# flea.net
KiCad netlist of a schematic drawn in EAGLE
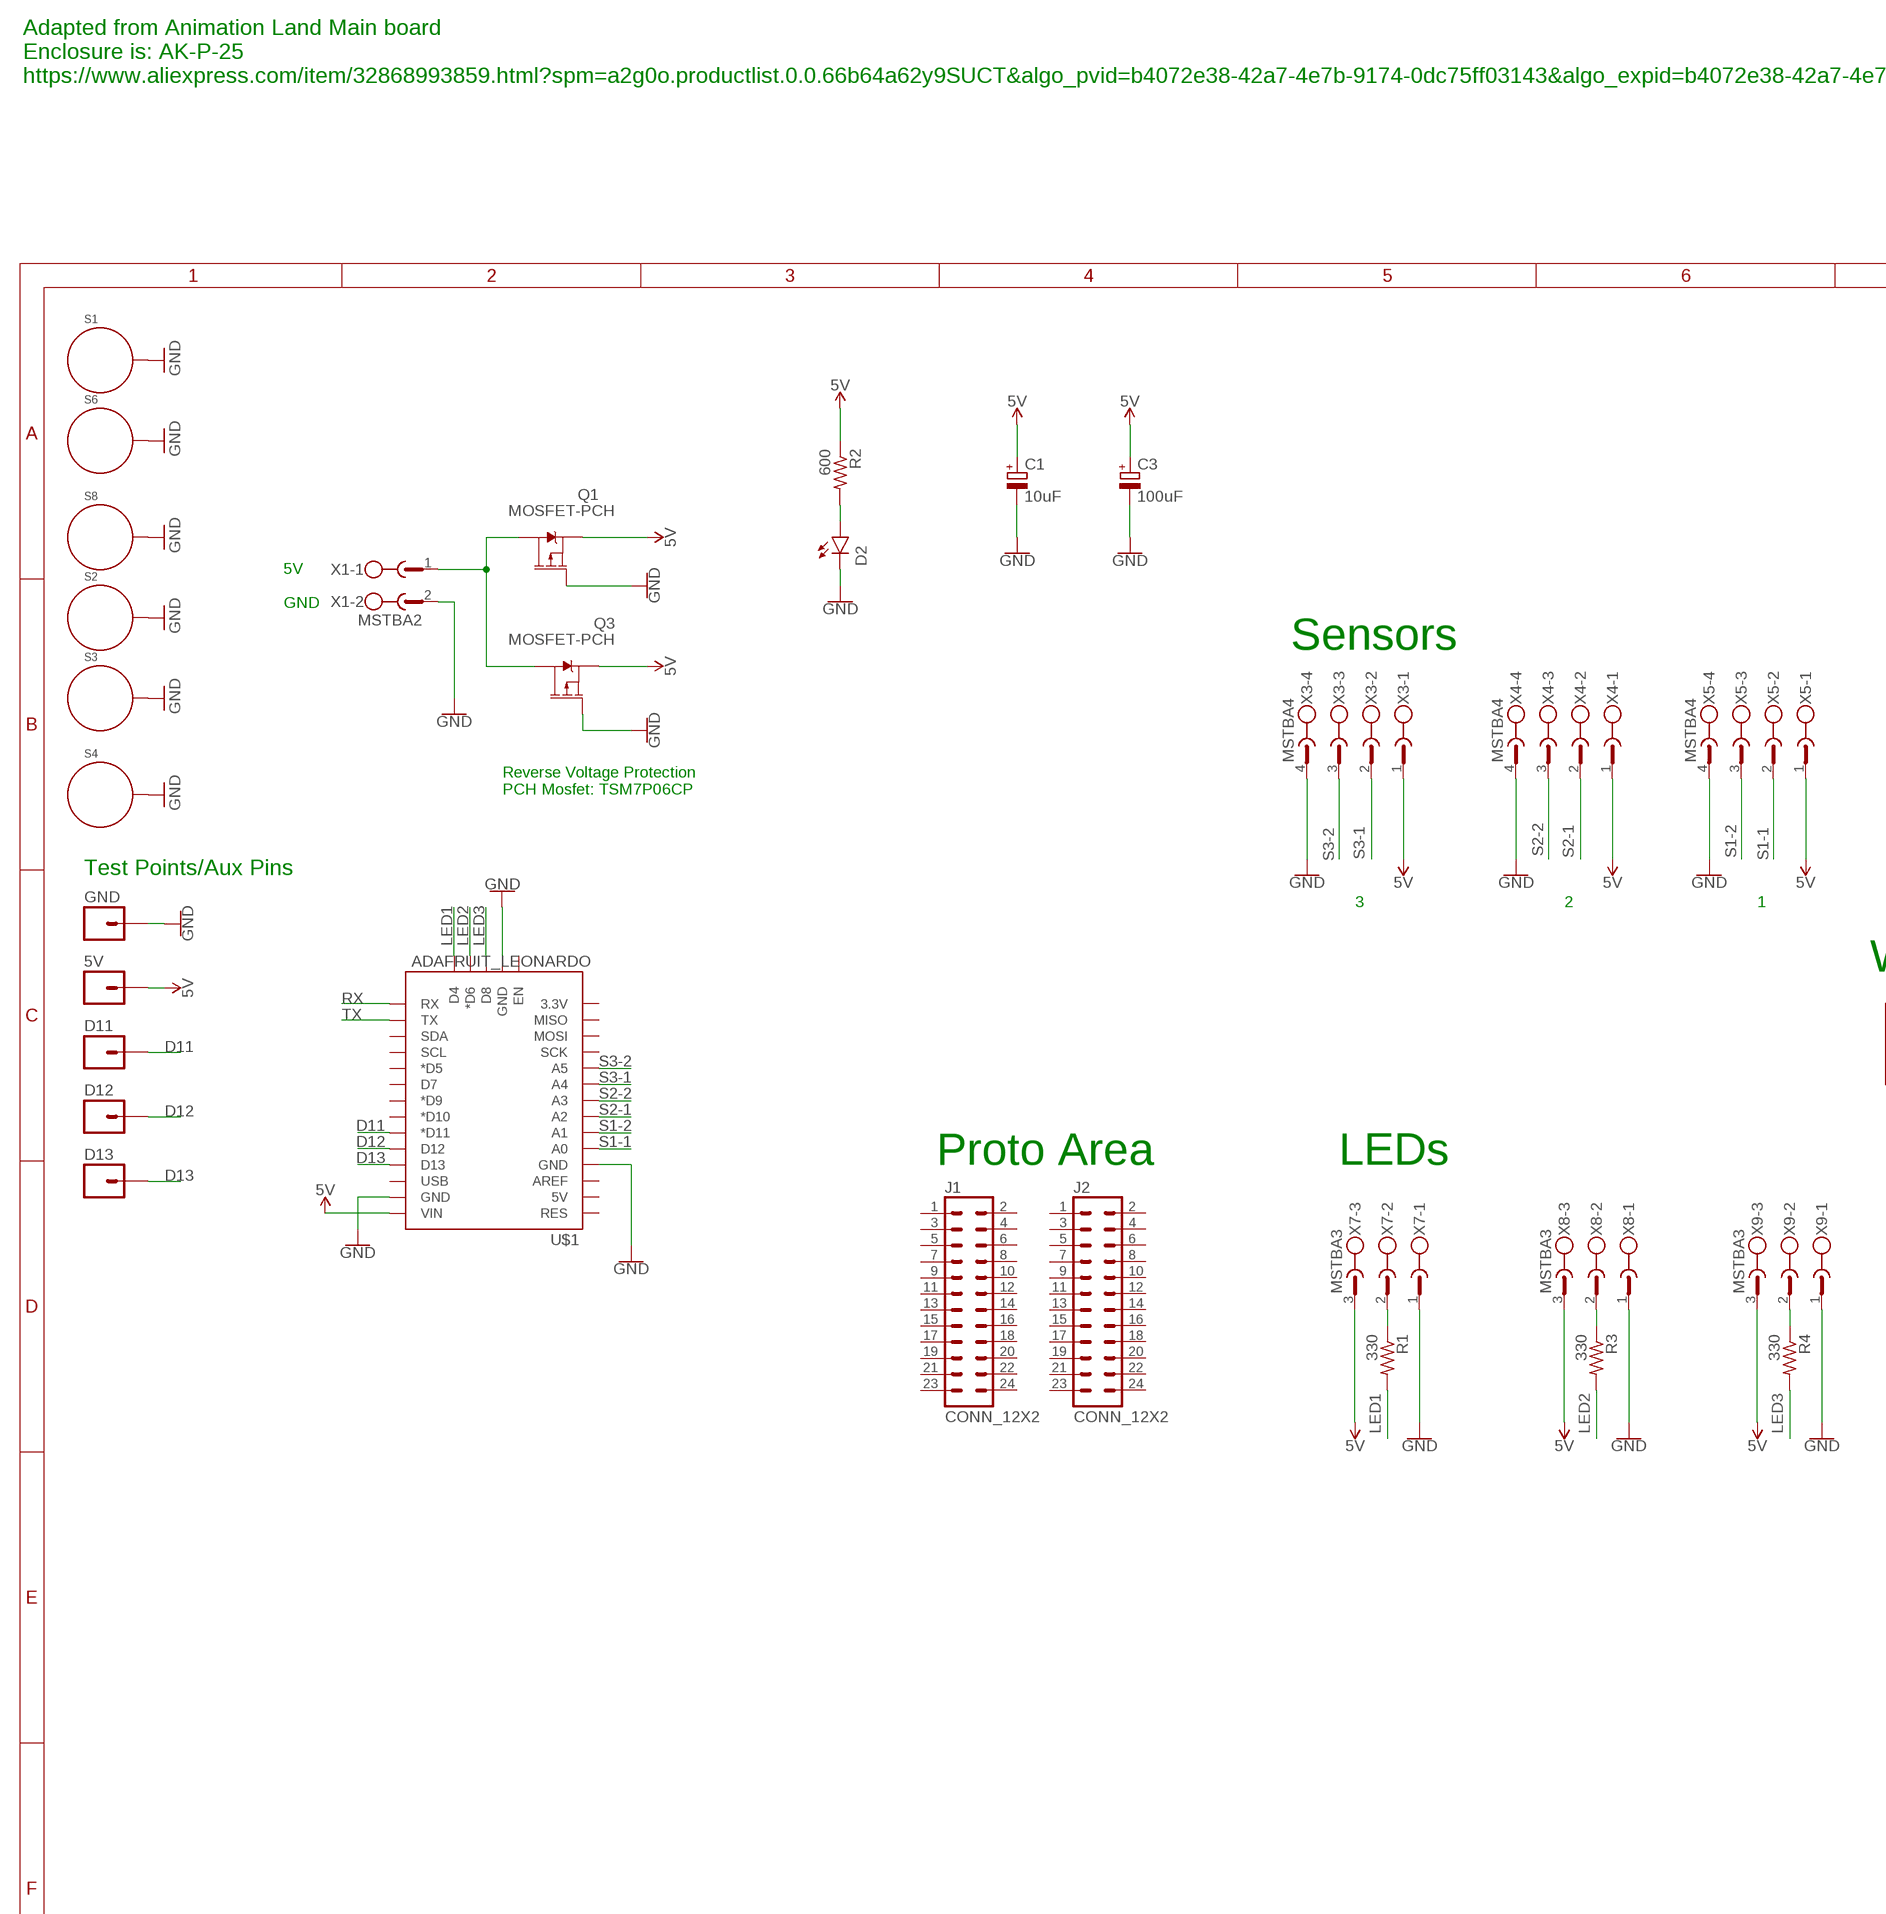
[diagram p0: schematic, sheet 1, part 1 of 2]
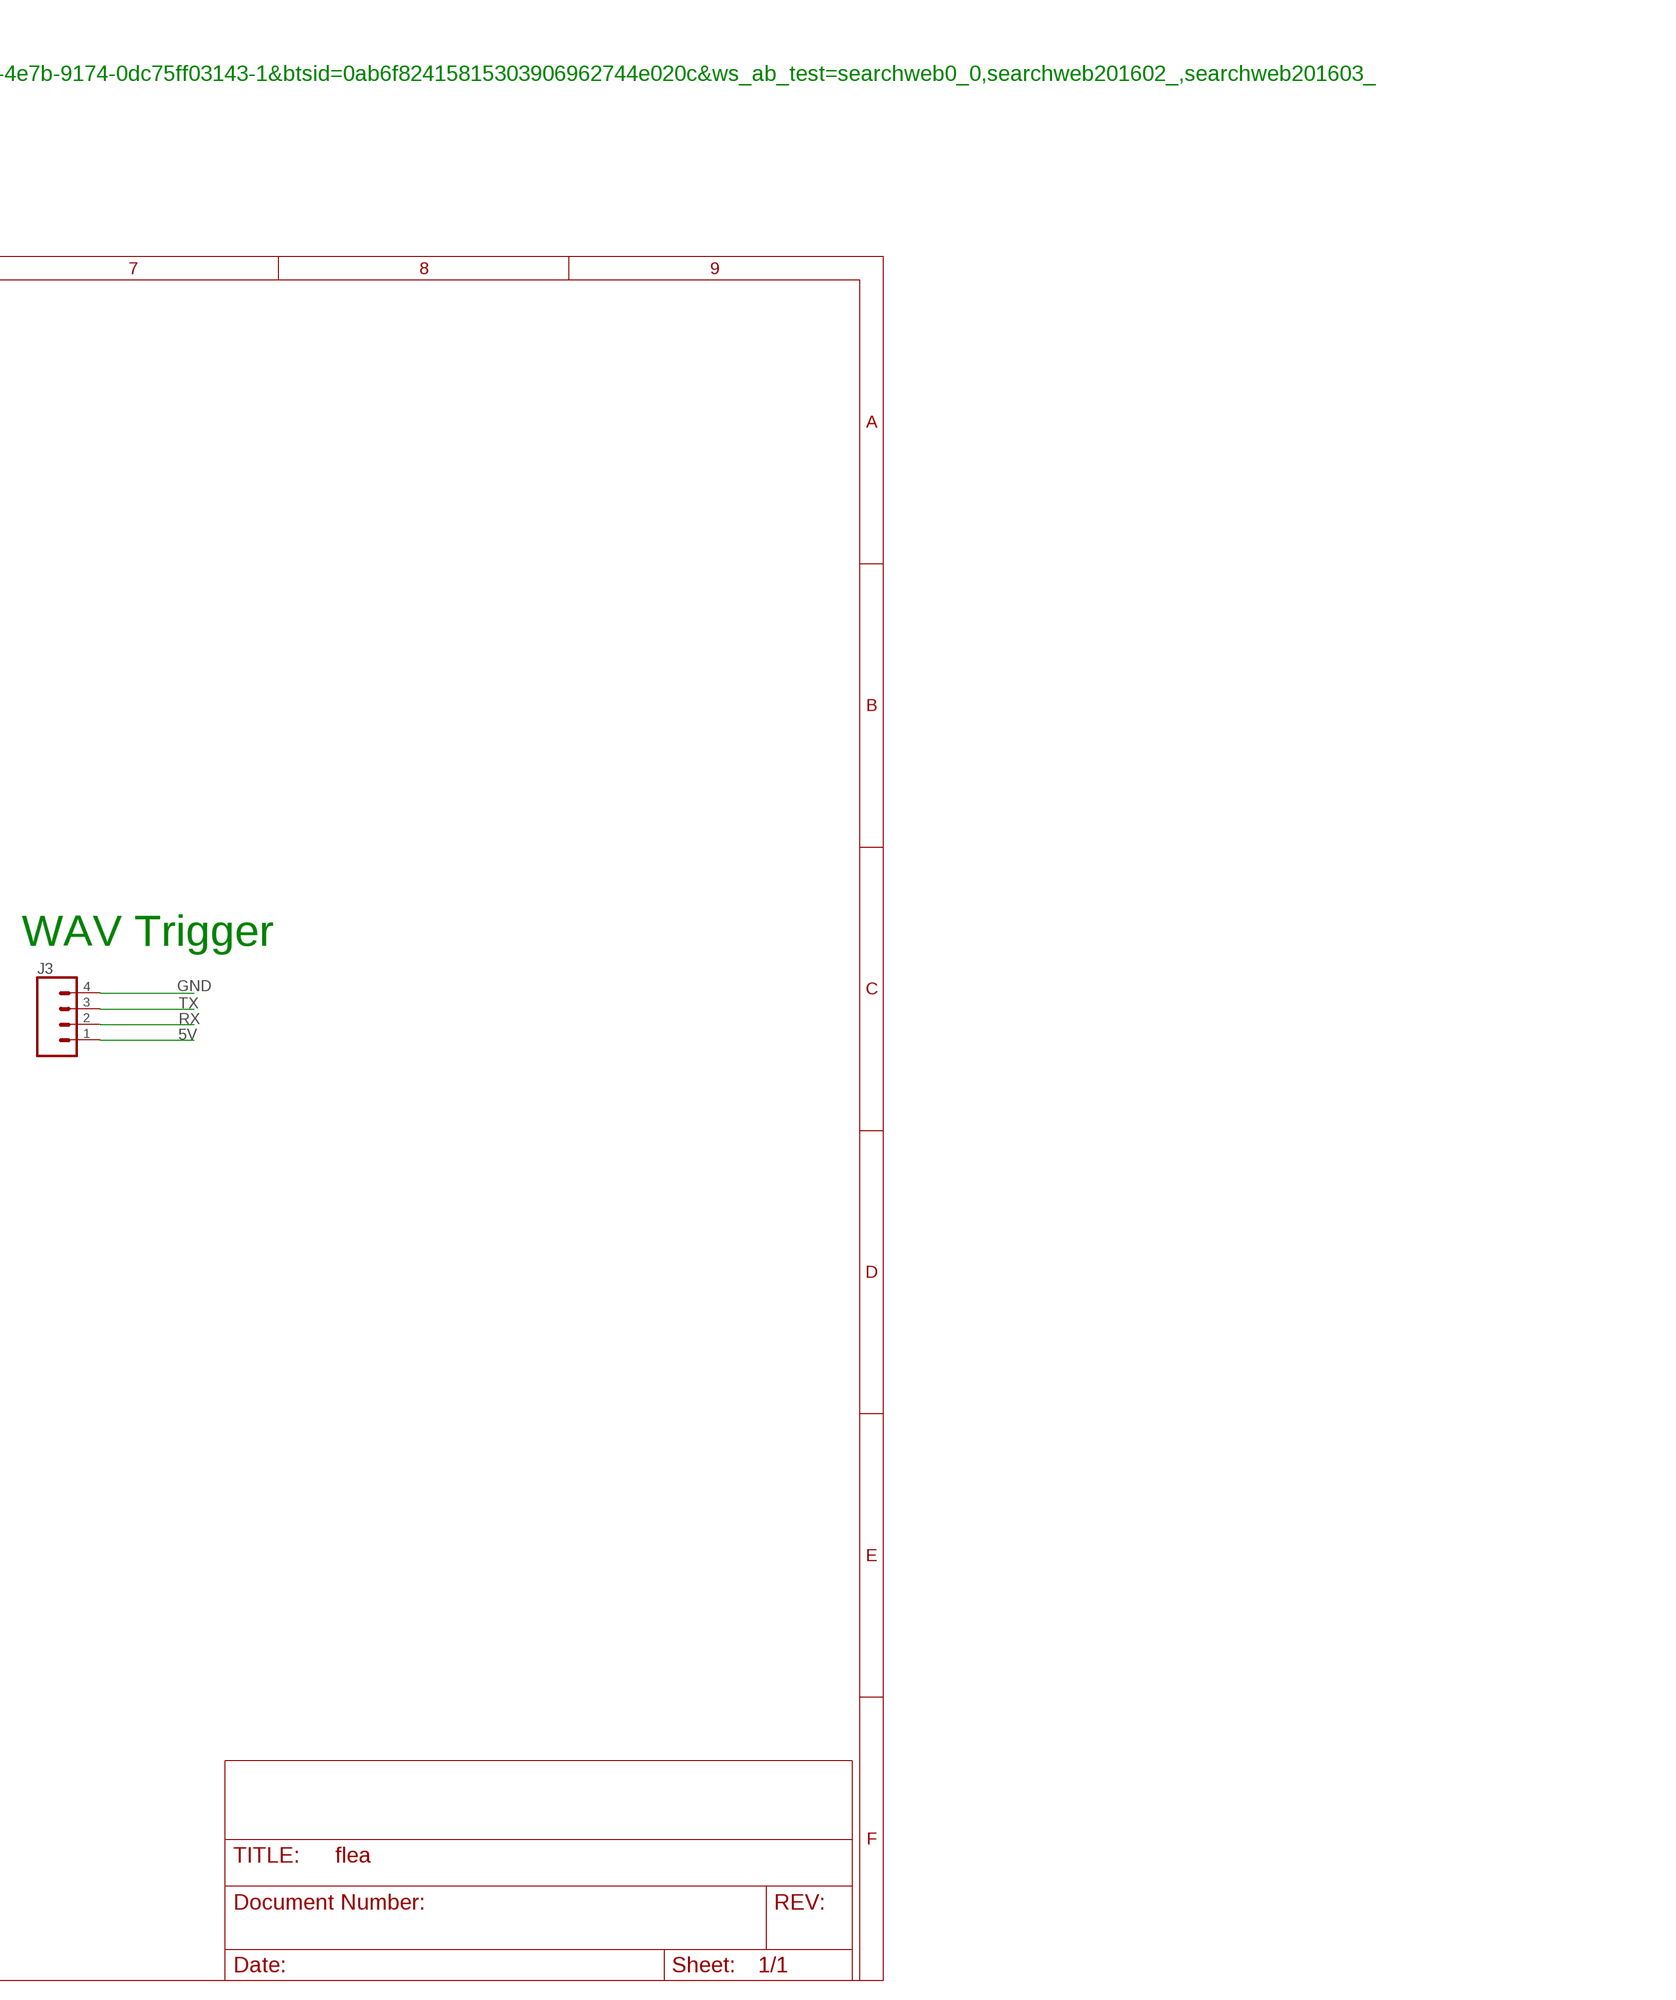
[diagram p1: schematic, sheet 1, part 2 of 2]

(export (version "E")
  (design (tool "Eeschema 10.0.6"))
  (components
    (comp (ref "5V")
      (value "M01PTH")
      (footprint "eagle-import:1X01")
      (libsource (lib "eagle-import") (part "M01PTH"))
    )
    (comp (ref "C1")
      (value "10uF")
      (footprint "eagle-import:E2-5")
      (libsource (lib "eagle-import") (part "CPOL-EUE2-5"))
    )
    (comp (ref "C3")
      (value "100uF")
      (footprint "eagle-import:E3,5-10")
      (libsource (lib "eagle-import") (part "CPOL-EUE3.5-10"))
    )
    (comp (ref "D2")
      (value "RED")
      (footprint "eagle-import:SPARKFUN-LED_LED-1206")
      (libsource (lib "eagle-import") (part "SPARKFUN-LED_LED1206"))
    )
    (comp (ref "D11")
      (value "M01PTH")
      (footprint "eagle-import:1X01")
      (libsource (lib "eagle-import") (part "M01PTH"))
    )
    (comp (ref "D12")
      (value "M01PTH")
      (footprint "eagle-import:1X01")
      (libsource (lib "eagle-import") (part "M01PTH"))
    )
    (comp (ref "D13")
      (value "M01PTH")
      (footprint "eagle-import:1X01")
      (libsource (lib "eagle-import") (part "M01PTH"))
    )
    (comp (ref "GND")
      (value "M01PTH")
      (footprint "eagle-import:1X01")
      (libsource (lib "eagle-import") (part "M01PTH"))
    )
    (comp (ref "J1")
      (value "CONN_12X2")
      (footprint "eagle-import:2X12")
      (libsource (lib "eagle-import") (part "CONN_12X2"))
    )
    (comp (ref "J2")
      (value "CONN_12X2")
      (footprint "eagle-import:2X12")
      (libsource (lib "eagle-import") (part "CONN_12X2"))
    )
    (comp (ref "J3")
      (value "CONN_043.5MM_RA")
      (footprint "eagle-import:1X04_3.5MM_RA")
      (libsource (lib "eagle-import") (part "CONN_043.5MM_RA"))
    )
    (comp (ref "Q1")
      (value "MOSFET-PCH")
      (footprint "eagle-import:DPAK")
      (libsource (lib "eagle-import") (part "MOSFET-PCH"))
    )
    (comp (ref "Q3")
      (value "MOSFET-PCH")
      (footprint "eagle-import:DPAK")
      (libsource (lib "eagle-import") (part "MOSFET-PCH"))
    )
    (comp (ref "R1")
      (value "330")
      (footprint "eagle-import:R0805")
      (libsource (lib "eagle-import") (part "R-US_R0805"))
    )
    (comp (ref "R2")
      (value "600")
      (footprint "eagle-import:R0805")
      (libsource (lib "eagle-import") (part "R-US_R0805"))
    )
    (comp (ref "R3")
      (value "330")
      (footprint "eagle-import:R0805")
      (libsource (lib "eagle-import") (part "R-US_R0805"))
    )
    (comp (ref "R4")
      (value "330")
      (footprint "eagle-import:R0805")
      (libsource (lib "eagle-import") (part "R-US_R0805"))
    )
    (comp (ref "S1")
      (value "STANDOFF_ELECTRICAL5-32")
      (footprint "eagle-import:STANDOFF_ELECTRICAL_5_32")
      (libsource (lib "eagle-import") (part "STANDOFF_ELECTRICAL5-32"))
    )
    (comp (ref "S2")
      (value "STANDOFF_ELECTRICAL5-32")
      (footprint "eagle-import:STANDOFF_ELECTRICAL_5_32")
      (libsource (lib "eagle-import") (part "STANDOFF_ELECTRICAL5-32"))
    )
    (comp (ref "S3")
      (value "STANDOFF_ELECTRICAL5-32")
      (footprint "eagle-import:STANDOFF_ELECTRICAL_5_32")
      (libsource (lib "eagle-import") (part "STANDOFF_ELECTRICAL5-32"))
    )
    (comp (ref "S4")
      (value "STANDOFF_ELECTRICAL5-32")
      (footprint "eagle-import:STANDOFF_ELECTRICAL_5_32")
      (libsource (lib "eagle-import") (part "STANDOFF_ELECTRICAL5-32"))
    )
    (comp (ref "S6")
      (value "STANDOFF_ELECTRICAL5-32")
      (footprint "eagle-import:STANDOFF_ELECTRICAL_5_32")
      (libsource (lib "eagle-import") (part "STANDOFF_ELECTRICAL5-32"))
    )
    (comp (ref "S8")
      (value "STANDOFF_ELECTRICAL5-32")
      (footprint "eagle-import:STANDOFF_ELECTRICAL_5_32")
      (libsource (lib "eagle-import") (part "STANDOFF_ELECTRICAL5-32"))
    )
    (comp (ref "U$1")
      (value "ADAFRUIT_LEONARDO")
      (footprint "eagle-import:ADAFRUIT_LENOARDO")
      (libsource (lib "eagle-import") (part "ADAFRUIT_LEONARDO"))
    )
    (comp (ref "X1")
      (value "MSTBA2")
      (footprint "eagle-import:MSTBA2")
      (fields (field (name "MF") "FARNELL") (field (name "MPN") "1757242"))
      (libsource (lib "eagle-import") (part "MSTBA2"))
    )
    (comp (ref "X3")
      (value "MSTBA4")
      (footprint "eagle-import:MSTBA4")
      (fields (field (name "MF") "FARNELL") (field (name "MPN") "1757268"))
      (libsource (lib "eagle-import") (part "MSTBA4"))
    )
    (comp (ref "X4")
      (value "MSTBA4")
      (footprint "eagle-import:MSTBA4")
      (fields (field (name "MF") "FARNELL") (field (name "MPN") "1757268"))
      (libsource (lib "eagle-import") (part "MSTBA4"))
    )
    (comp (ref "X5")
      (value "MSTBA4")
      (footprint "eagle-import:MSTBA4")
      (fields (field (name "MF") "FARNELL") (field (name "MPN") "1757268"))
      (libsource (lib "eagle-import") (part "MSTBA4"))
    )
    (comp (ref "X7")
      (value "MSTBA3")
      (footprint "eagle-import:MSTBA3")
      (fields (field (name "MF") "FARNELL") (field (name "MPN") "1757255"))
      (libsource (lib "eagle-import") (part "MSTBA3"))
    )
    (comp (ref "X8")
      (value "MSTBA3")
      (footprint "eagle-import:MSTBA3")
      (fields (field (name "MF") "FARNELL") (field (name "MPN") "1757255"))
      (libsource (lib "eagle-import") (part "MSTBA3"))
    )
    (comp (ref "X9")
      (value "MSTBA3")
      (footprint "eagle-import:MSTBA3")
      (fields (field (name "MF") "FARNELL") (field (name "MPN") "1757255"))
      (libsource (lib "eagle-import") (part "MSTBA3"))
    )
  )
  (nets
    (net (code "1") (name "/D11") (class "Default")
      (node (ref "D11") (pin "1") (pinfunction "1_1") (pintype "passive"))
      (node (ref "U$1") (pin "D11") (pinfunction "*D11_D11") (pintype "bidirectional"))
    )
    (net (code "2") (name "/D12") (class "Default")
      (node (ref "D12") (pin "1") (pinfunction "1_1") (pintype "passive"))
      (node (ref "U$1") (pin "D12") (pinfunction "D12_D12") (pintype "bidirectional"))
    )
    (net (code "3") (name "/D13") (class "Default")
      (node (ref "D13") (pin "1") (pinfunction "1_1") (pintype "passive"))
      (node (ref "U$1") (pin "D13") (pinfunction "D13_D13") (pintype "bidirectional"))
    )
    (net (code "4") (name "/LED1") (class "Default")
      (node (ref "R1") (pin "2") (pinfunction "2_2") (pintype "passive"))
      (node (ref "U$1") (pin "D4") (pinfunction "D4_D4") (pintype "bidirectional"))
    )
    (net (code "5") (name "/LED2") (class "Default")
      (node (ref "R3") (pin "2") (pinfunction "2_2") (pintype "passive"))
      (node (ref "U$1") (pin "D6") (pinfunction "*D6_D6") (pintype "bidirectional"))
    )
    (net (code "6") (name "/LED3") (class "Default")
      (node (ref "R4") (pin "2") (pinfunction "2_2") (pintype "passive"))
      (node (ref "U$1") (pin "D8") (pinfunction "D8_D8") (pintype "bidirectional"))
    )
    (net (code "7") (name "/RX") (class "Default")
      (node (ref "J3") (pin "2") (pinfunction "2_2") (pintype "passive"))
      (node (ref "U$1") (pin "RX") (pinfunction "RX_RX") (pintype "bidirectional"))
    )
    (net (code "8") (name "/S1-1") (class "Default")
      (node (ref "U$1") (pin "A0") (pinfunction "A0_A0") (pintype "bidirectional"))
      (node (ref "X5") (pin "2") (pinfunction "1_2") (pintype "passive"))
    )
    (net (code "9") (name "/S1-2") (class "Default")
      (node (ref "U$1") (pin "A1") (pinfunction "A1_A1") (pintype "bidirectional"))
      (node (ref "X5") (pin "3") (pinfunction "1_3") (pintype "passive"))
    )
    (net (code "10") (name "/S2-1") (class "Default")
      (node (ref "U$1") (pin "A2") (pinfunction "A2_A2") (pintype "bidirectional"))
      (node (ref "X4") (pin "2") (pinfunction "1_2") (pintype "passive"))
    )
    (net (code "11") (name "/S2-2") (class "Default")
      (node (ref "U$1") (pin "A3") (pinfunction "A3_A3") (pintype "bidirectional"))
      (node (ref "X4") (pin "3") (pinfunction "1_3") (pintype "passive"))
    )
    (net (code "12") (name "/S3-1") (class "Default")
      (node (ref "U$1") (pin "A4") (pinfunction "A4_A4") (pintype "bidirectional"))
      (node (ref "X3") (pin "2") (pinfunction "1_2") (pintype "passive"))
    )
    (net (code "13") (name "/S3-2") (class "Default")
      (node (ref "U$1") (pin "A5") (pinfunction "A5_A5") (pintype "bidirectional"))
      (node (ref "X3") (pin "3") (pinfunction "1_3") (pintype "passive"))
    )
    (net (code "14") (name "/TX") (class "Default")
      (node (ref "J3") (pin "3") (pinfunction "3_3") (pintype "passive"))
      (node (ref "U$1") (pin "TX") (pinfunction "TX_TX") (pintype "bidirectional"))
    )
    (net (code "15") (name "5V") (class "Default")
      (node (ref "5V") (pin "1") (pinfunction "1_1") (pintype "passive"))
      (node (ref "C1") (pin "+") (pinfunction "+_+") (pintype "passive"))
      (node (ref "C3") (pin "+") (pinfunction "+_+") (pintype "passive"))
      (node (ref "J3") (pin "1") (pinfunction "1_1") (pintype "passive"))
      (node (ref "Q1") (pin "3") (pinfunction "S_3") (pintype "bidirectional"))
      (node (ref "Q3") (pin "3") (pinfunction "S_3") (pintype "bidirectional"))
      (node (ref "R2") (pin "1") (pinfunction "1_1") (pintype "passive"))
      (node (ref "U$1") (pin "VIN") (pinfunction "VIN_VIN") (pintype "bidirectional"))
      (node (ref "X3") (pin "1") (pinfunction "1_1") (pintype "passive"))
      (node (ref "X4") (pin "1") (pinfunction "1_1") (pintype "passive"))
      (node (ref "X5") (pin "1") (pinfunction "1_1") (pintype "passive"))
      (node (ref "X7") (pin "3") (pinfunction "1_3") (pintype "passive"))
      (node (ref "X8") (pin "3") (pinfunction "1_3") (pintype "passive"))
      (node (ref "X9") (pin "3") (pinfunction "1_3") (pintype "passive"))
    )
    (net (code "16") (name "GND") (class "Default")
      (node (ref "C1") (pin "-") (pinfunction "-_-") (pintype "passive"))
      (node (ref "C3") (pin "-") (pinfunction "-_-") (pintype "passive"))
      (node (ref "D2") (pin "C") (pinfunction "C_C") (pintype "passive"))
      (node (ref "GND") (pin "1") (pinfunction "1_1") (pintype "passive"))
      (node (ref "J3") (pin "4") (pinfunction "4_4") (pintype "passive"))
      (node (ref "Q1") (pin "1") (pinfunction "G_1") (pintype "bidirectional"))
      (node (ref "Q3") (pin "1") (pinfunction "G_1") (pintype "bidirectional"))
      (node (ref "S1") (pin "P1") (pinfunction "P$1_P1") (pintype "bidirectional"))
      (node (ref "S2") (pin "P1") (pinfunction "P$1_P1") (pintype "bidirectional"))
      (node (ref "S3") (pin "P1") (pinfunction "P$1_P1") (pintype "bidirectional"))
      (node (ref "S4") (pin "P1") (pinfunction "P$1_P1") (pintype "bidirectional"))
      (node (ref "S6") (pin "P1") (pinfunction "P$1_P1") (pintype "bidirectional"))
      (node (ref "S8") (pin "P1") (pinfunction "P$1_P1") (pintype "bidirectional"))
      (node (ref "U$1") (pin "GND@0") (pinfunction "GND_GND@0") (pintype "bidirectional"))
      (node (ref "U$1") (pin "GND@1") (pinfunction "GND_GND@1") (pintype "bidirectional"))
      (node (ref "U$1") (pin "GND@2") (pinfunction "GND_GND@2") (pintype "bidirectional"))
      (node (ref "X1") (pin "2") (pinfunction "1_2") (pintype "passive"))
      (node (ref "X3") (pin "4") (pinfunction "1_4") (pintype "passive"))
      (node (ref "X4") (pin "4") (pinfunction "1_4") (pintype "passive"))
      (node (ref "X5") (pin "4") (pinfunction "1_4") (pintype "passive"))
      (node (ref "X7") (pin "1") (pinfunction "1_1") (pintype "passive"))
      (node (ref "X8") (pin "1") (pinfunction "1_1") (pintype "passive"))
      (node (ref "X9") (pin "1") (pinfunction "1_1") (pintype "passive"))
    )
    (net (code "17") (name "Net-(D2-PadA)") (class "Default")
      (node (ref "D2") (pin "A") (pinfunction "A_A") (pintype "passive"))
      (node (ref "R2") (pin "2") (pinfunction "2_2") (pintype "passive"))
    )
    (net (code "18") (name "Net-(Q1-D)") (class "Default")
      (node (ref "Q1") (pin "4") (pinfunction "D_4") (pintype "bidirectional"))
      (node (ref "Q3") (pin "4") (pinfunction "D_4") (pintype "bidirectional"))
      (node (ref "X1") (pin "1") (pinfunction "1_1") (pintype "passive"))
    )
    (net (code "19") (name "Net-(X7B-1)") (class "Default")
      (node (ref "R1") (pin "1") (pinfunction "1_1") (pintype "passive"))
      (node (ref "X7") (pin "2") (pinfunction "1_2") (pintype "passive"))
    )
    (net (code "20") (name "Net-(X8B-1)") (class "Default")
      (node (ref "R3") (pin "1") (pinfunction "1_1") (pintype "passive"))
      (node (ref "X8") (pin "2") (pinfunction "1_2") (pintype "passive"))
    )
    (net (code "21") (name "Net-(X9B-1)") (class "Default")
      (node (ref "R4") (pin "1") (pinfunction "1_1") (pintype "passive"))
      (node (ref "X9") (pin "2") (pinfunction "1_2") (pintype "passive"))
    )
    (net (code "22") (name "unconnected-(J1-Pad1)") (class "Default")
      (node (ref "J1") (pin "1") (pinfunction "1_1") (pintype "passive"))
    )
    (net (code "23") (name "unconnected-(J1-Pad2)") (class "Default")
      (node (ref "J1") (pin "2") (pinfunction "2_2") (pintype "passive"))
    )
    (net (code "24") (name "unconnected-(J1-Pad3)") (class "Default")
      (node (ref "J1") (pin "3") (pinfunction "3_3") (pintype "passive"))
    )
    (net (code "25") (name "unconnected-(J1-Pad4)") (class "Default")
      (node (ref "J1") (pin "4") (pinfunction "4_4") (pintype "passive"))
    )
    (net (code "26") (name "unconnected-(J1-Pad5)") (class "Default")
      (node (ref "J1") (pin "5") (pinfunction "5_5") (pintype "passive"))
    )
    (net (code "27") (name "unconnected-(J1-Pad6)") (class "Default")
      (node (ref "J1") (pin "6") (pinfunction "6_6") (pintype "passive"))
    )
    (net (code "28") (name "unconnected-(J1-Pad7)") (class "Default")
      (node (ref "J1") (pin "7") (pinfunction "7_7") (pintype "passive"))
    )
    (net (code "29") (name "unconnected-(J1-Pad8)") (class "Default")
      (node (ref "J1") (pin "8") (pinfunction "8_8") (pintype "passive"))
    )
    (net (code "30") (name "unconnected-(J1-Pad9)") (class "Default")
      (node (ref "J1") (pin "9") (pinfunction "9_9") (pintype "passive"))
    )
    (net (code "31") (name "unconnected-(J1-Pad10)") (class "Default")
      (node (ref "J1") (pin "10") (pinfunction "10_10") (pintype "passive"))
    )
    (net (code "32") (name "unconnected-(J1-Pad11)") (class "Default")
      (node (ref "J1") (pin "11") (pinfunction "11_11") (pintype "passive"))
    )
    (net (code "33") (name "unconnected-(J1-Pad12)") (class "Default")
      (node (ref "J1") (pin "12") (pinfunction "12_12") (pintype "passive"))
    )
    (net (code "34") (name "unconnected-(J1-Pad13)") (class "Default")
      (node (ref "J1") (pin "13") (pinfunction "13_13") (pintype "passive"))
    )
    (net (code "35") (name "unconnected-(J1-Pad14)") (class "Default")
      (node (ref "J1") (pin "14") (pinfunction "14_14") (pintype "passive"))
    )
    (net (code "36") (name "unconnected-(J1-Pad15)") (class "Default")
      (node (ref "J1") (pin "15") (pinfunction "15_15") (pintype "passive"))
    )
    (net (code "37") (name "unconnected-(J1-Pad16)") (class "Default")
      (node (ref "J1") (pin "16") (pinfunction "16_16") (pintype "passive"))
    )
    (net (code "38") (name "unconnected-(J1-Pad17)") (class "Default")
      (node (ref "J1") (pin "17") (pinfunction "17_17") (pintype "passive"))
    )
    (net (code "39") (name "unconnected-(J1-Pad18)") (class "Default")
      (node (ref "J1") (pin "18") (pinfunction "18_18") (pintype "passive"))
    )
    (net (code "40") (name "unconnected-(J1-Pad19)") (class "Default")
      (node (ref "J1") (pin "19") (pinfunction "19_19") (pintype "passive"))
    )
    (net (code "41") (name "unconnected-(J1-Pad20)") (class "Default")
      (node (ref "J1") (pin "20") (pinfunction "20_20") (pintype "passive"))
    )
    (net (code "42") (name "unconnected-(J1-Pad21)") (class "Default")
      (node (ref "J1") (pin "21") (pinfunction "21_21") (pintype "passive"))
    )
    (net (code "43") (name "unconnected-(J1-Pad22)") (class "Default")
      (node (ref "J1") (pin "22") (pinfunction "22_22") (pintype "passive"))
    )
    (net (code "44") (name "unconnected-(J1-Pad23)") (class "Default")
      (node (ref "J1") (pin "23") (pinfunction "23_23") (pintype "passive"))
    )
    (net (code "45") (name "unconnected-(J1-Pad24)") (class "Default")
      (node (ref "J1") (pin "24") (pinfunction "24_24") (pintype "passive"))
    )
    (net (code "46") (name "unconnected-(J2-Pad1)") (class "Default")
      (node (ref "J2") (pin "1") (pinfunction "1_1") (pintype "passive"))
    )
    (net (code "47") (name "unconnected-(J2-Pad2)") (class "Default")
      (node (ref "J2") (pin "2") (pinfunction "2_2") (pintype "passive"))
    )
    (net (code "48") (name "unconnected-(J2-Pad3)") (class "Default")
      (node (ref "J2") (pin "3") (pinfunction "3_3") (pintype "passive"))
    )
    (net (code "49") (name "unconnected-(J2-Pad4)") (class "Default")
      (node (ref "J2") (pin "4") (pinfunction "4_4") (pintype "passive"))
    )
    (net (code "50") (name "unconnected-(J2-Pad5)") (class "Default")
      (node (ref "J2") (pin "5") (pinfunction "5_5") (pintype "passive"))
    )
    (net (code "51") (name "unconnected-(J2-Pad6)") (class "Default")
      (node (ref "J2") (pin "6") (pinfunction "6_6") (pintype "passive"))
    )
    (net (code "52") (name "unconnected-(J2-Pad7)") (class "Default")
      (node (ref "J2") (pin "7") (pinfunction "7_7") (pintype "passive"))
    )
    (net (code "53") (name "unconnected-(J2-Pad8)") (class "Default")
      (node (ref "J2") (pin "8") (pinfunction "8_8") (pintype "passive"))
    )
    (net (code "54") (name "unconnected-(J2-Pad9)") (class "Default")
      (node (ref "J2") (pin "9") (pinfunction "9_9") (pintype "passive"))
    )
    (net (code "55") (name "unconnected-(J2-Pad10)") (class "Default")
      (node (ref "J2") (pin "10") (pinfunction "10_10") (pintype "passive"))
    )
    (net (code "56") (name "unconnected-(J2-Pad11)") (class "Default")
      (node (ref "J2") (pin "11") (pinfunction "11_11") (pintype "passive"))
    )
    (net (code "57") (name "unconnected-(J2-Pad12)") (class "Default")
      (node (ref "J2") (pin "12") (pinfunction "12_12") (pintype "passive"))
    )
    (net (code "58") (name "unconnected-(J2-Pad13)") (class "Default")
      (node (ref "J2") (pin "13") (pinfunction "13_13") (pintype "passive"))
    )
    (net (code "59") (name "unconnected-(J2-Pad14)") (class "Default")
      (node (ref "J2") (pin "14") (pinfunction "14_14") (pintype "passive"))
    )
    (net (code "60") (name "unconnected-(J2-Pad15)") (class "Default")
      (node (ref "J2") (pin "15") (pinfunction "15_15") (pintype "passive"))
    )
    (net (code "61") (name "unconnected-(J2-Pad16)") (class "Default")
      (node (ref "J2") (pin "16") (pinfunction "16_16") (pintype "passive"))
    )
    (net (code "62") (name "unconnected-(J2-Pad17)") (class "Default")
      (node (ref "J2") (pin "17") (pinfunction "17_17") (pintype "passive"))
    )
    (net (code "63") (name "unconnected-(J2-Pad18)") (class "Default")
      (node (ref "J2") (pin "18") (pinfunction "18_18") (pintype "passive"))
    )
    (net (code "64") (name "unconnected-(J2-Pad19)") (class "Default")
      (node (ref "J2") (pin "19") (pinfunction "19_19") (pintype "passive"))
    )
    (net (code "65") (name "unconnected-(J2-Pad20)") (class "Default")
      (node (ref "J2") (pin "20") (pinfunction "20_20") (pintype "passive"))
    )
    (net (code "66") (name "unconnected-(J2-Pad21)") (class "Default")
      (node (ref "J2") (pin "21") (pinfunction "21_21") (pintype "passive"))
    )
    (net (code "67") (name "unconnected-(J2-Pad22)") (class "Default")
      (node (ref "J2") (pin "22") (pinfunction "22_22") (pintype "passive"))
    )
    (net (code "68") (name "unconnected-(J2-Pad23)") (class "Default")
      (node (ref "J2") (pin "23") (pinfunction "23_23") (pintype "passive"))
    )
    (net (code "69") (name "unconnected-(J2-Pad24)") (class "Default")
      (node (ref "J2") (pin "24") (pinfunction "24_24") (pintype "passive"))
    )
    (net (code "70") (name "unconnected-(U$1-*D5-PadD5)") (class "Default")
      (node (ref "U$1") (pin "D5") (pinfunction "*D5_D5") (pintype "bidirectional"))
    )
    (net (code "71") (name "unconnected-(U$1-*D9-PadD9)") (class "Default")
      (node (ref "U$1") (pin "D9") (pinfunction "*D9_D9") (pintype "bidirectional"))
    )
    (net (code "72") (name "unconnected-(U$1-*D10-PadD10)") (class "Default")
      (node (ref "U$1") (pin "D10") (pinfunction "*D10_D10") (pintype "bidirectional"))
    )
    (net (code "73") (name "unconnected-(U$1-3.3V-Pad3V)") (class "Default")
      (node (ref "U$1") (pin "3V") (pinfunction "3.3V_3V") (pintype "bidirectional"))
    )
    (net (code "74") (name "unconnected-(U$1-Pad5V)") (class "Default")
      (node (ref "U$1") (pin "5V") (pinfunction "5V_5V") (pintype "bidirectional"))
    )
    (net (code "75") (name "unconnected-(U$1-PadAREF)") (class "Default")
      (node (ref "U$1") (pin "AREF") (pinfunction "AREF_AREF") (pintype "bidirectional"))
    )
    (net (code "76") (name "unconnected-(U$1-PadD7)") (class "Default")
      (node (ref "U$1") (pin "D7") (pinfunction "D7_D7") (pintype "bidirectional"))
    )
    (net (code "77") (name "unconnected-(U$1-PadEN)") (class "Default")
      (node (ref "U$1") (pin "EN") (pinfunction "EN_EN") (pintype "bidirectional"))
    )
    (net (code "78") (name "unconnected-(U$1-PadMISO)") (class "Default")
      (node (ref "U$1") (pin "MISO") (pinfunction "MISO_MISO") (pintype "bidirectional"))
    )
    (net (code "79") (name "unconnected-(U$1-PadMOSI)") (class "Default")
      (node (ref "U$1") (pin "MOSI") (pinfunction "MOSI_MOSI") (pintype "bidirectional"))
    )
    (net (code "80") (name "unconnected-(U$1-PadRES)") (class "Default")
      (node (ref "U$1") (pin "RES") (pinfunction "RES_RES") (pintype "bidirectional"))
    )
    (net (code "81") (name "unconnected-(U$1-PadSCK)") (class "Default")
      (node (ref "U$1") (pin "SCK") (pinfunction "SCK_SCK") (pintype "bidirectional"))
    )
    (net (code "82") (name "unconnected-(U$1-PadSCL)") (class "Default")
      (node (ref "U$1") (pin "SCL") (pinfunction "SCL_SCL") (pintype "bidirectional"))
    )
    (net (code "83") (name "unconnected-(U$1-PadSDA)") (class "Default")
      (node (ref "U$1") (pin "SDA") (pinfunction "SDA_SDA") (pintype "bidirectional"))
    )
    (net (code "84") (name "unconnected-(U$1-PadUSB)") (class "Default")
      (node (ref "U$1") (pin "USB") (pinfunction "USB_USB") (pintype "bidirectional"))
    )
  )
)
